# PiHatSandwich-v2.net
KiCad netlist of a schematic drawn in EAGLE
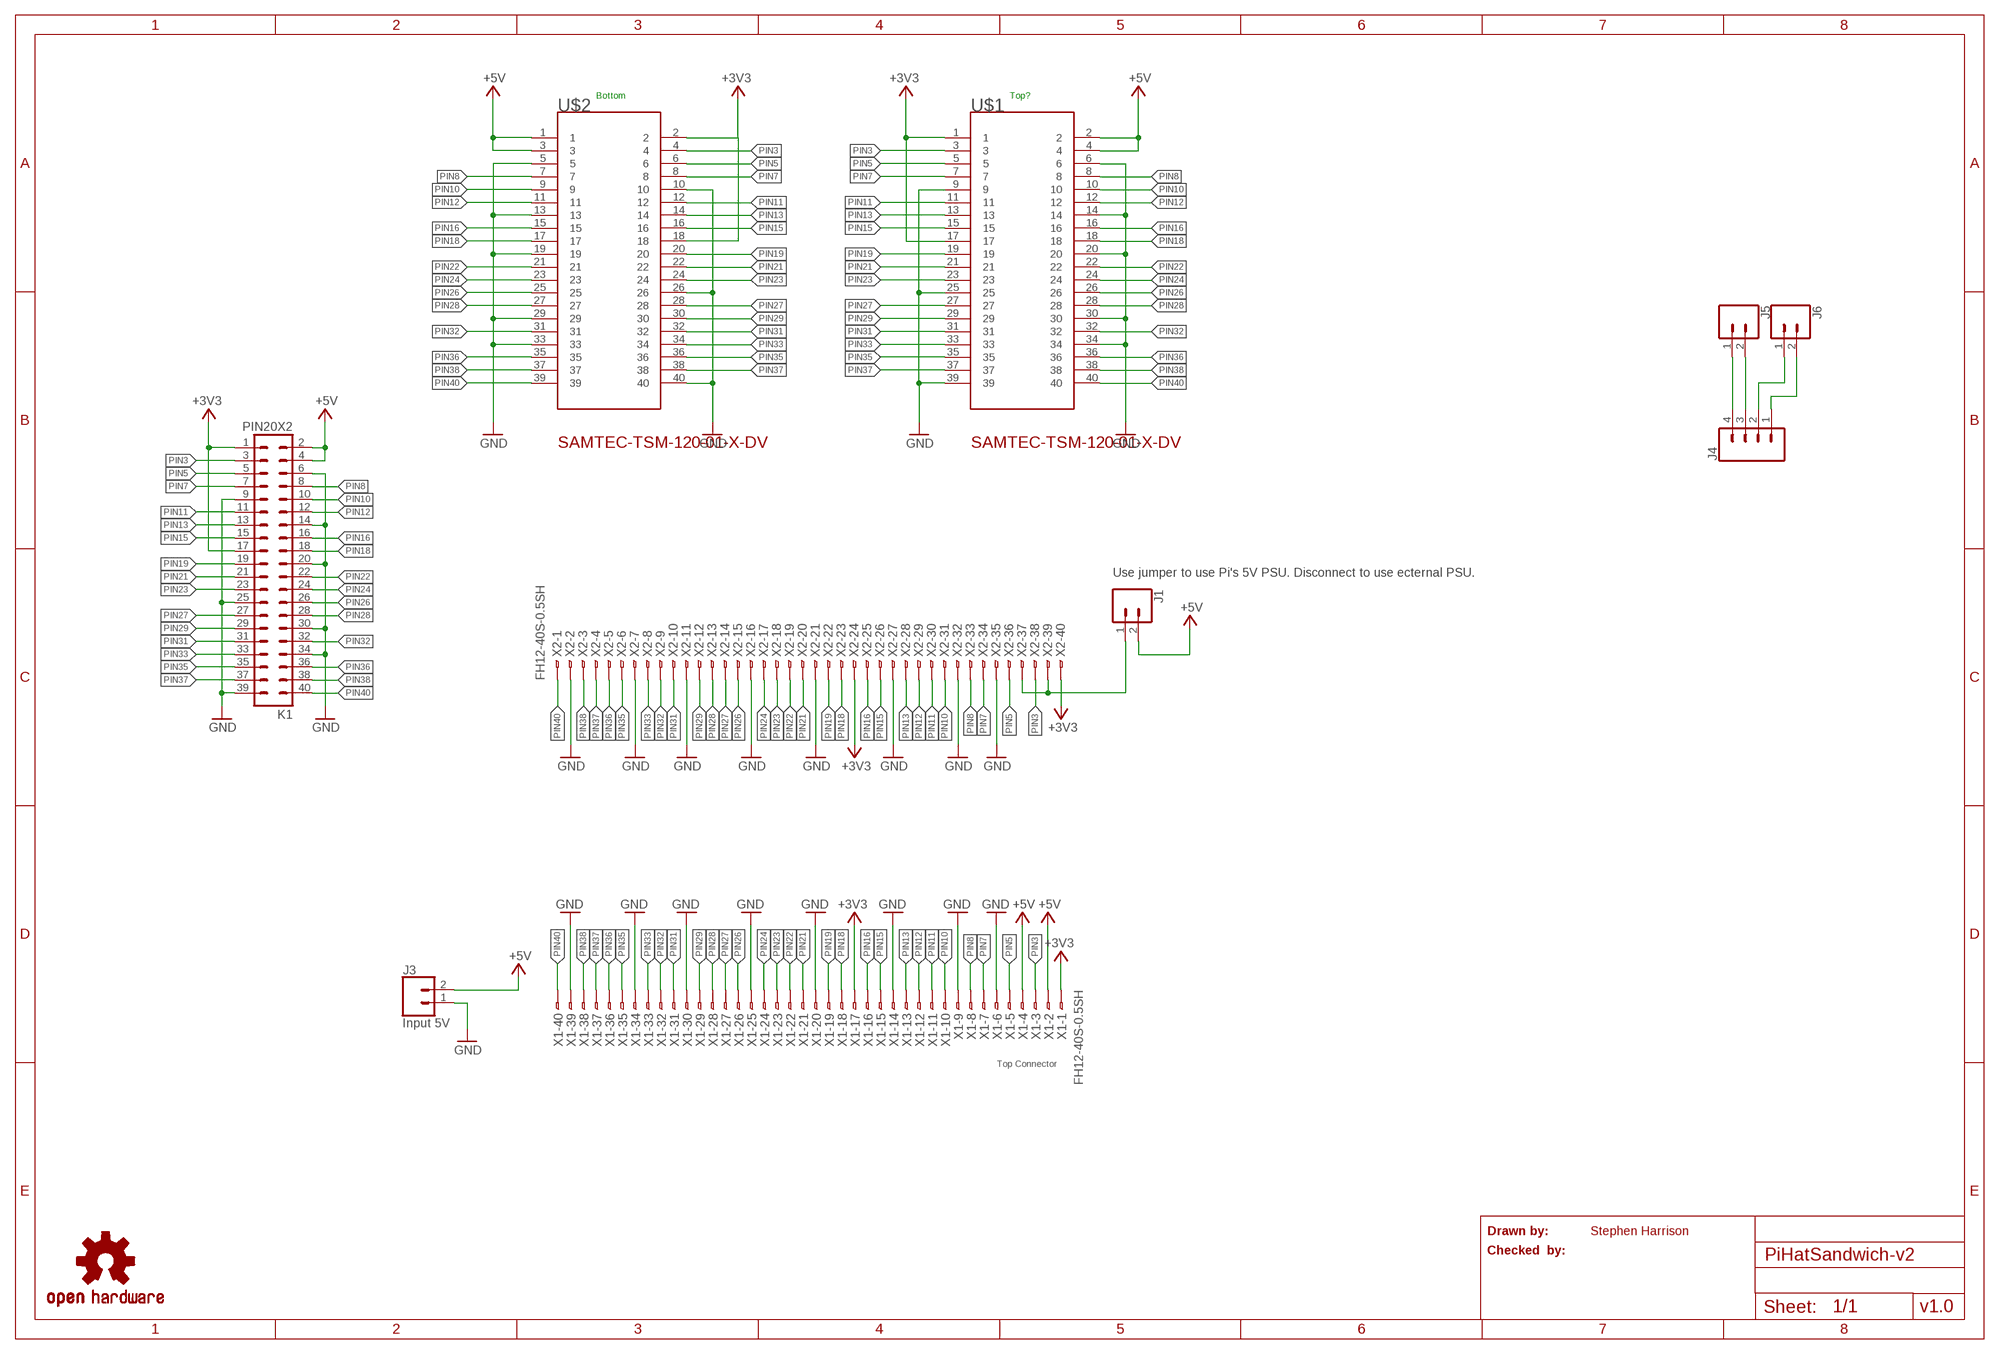
[diagram p0: schematic, sheet 1]

(export (version "E")
  (design (tool "Eeschema 10.0.6"))
  (components
    (comp (ref "J1")
      (value "CONN_02")
      (footprint "eagle-import:1X02")
      (libsource (lib "eagle-import") (part "CONN_02"))
    )
    (comp (ref "J3")
      (value "Input 5V")
      (footprint "eagle-import:MOLEX-1X2")
      (libsource (lib "eagle-import") (part "CONN_02POLAR"))
    )
    (comp (ref "J4")
      (value "CONN_04POLAR")
      (footprint "eagle-import:MOLEX-1X4")
      (libsource (lib "eagle-import") (part "CONN_04POLAR"))
    )
    (comp (ref "J5")
      (value "CONN_02")
      (footprint "eagle-import:1X02")
      (libsource (lib "eagle-import") (part "CONN_02"))
    )
    (comp (ref "J6")
      (value "CONN_02")
      (footprint "eagle-import:1X02")
      (libsource (lib "eagle-import") (part "CONN_02"))
    )
    (comp (ref "K1")
      (value "PIN20X2")
      (footprint "eagle-import:PIN_20X2")
      (libsource (lib "eagle-import") (part "PIN20X2"))
    )
    (comp (ref "LOGO1")
      (value "OSHW-LOGOL")
      (footprint "eagle-import:OSHW-LOGO-L")
      (libsource (lib "eagle-import") (part "OSHW-LOGOL"))
    )
    (comp (ref "U$1")
      (value "SAMTEC-TSM-120-01-X-DVJ")
      (footprint "eagle-import:SAMTEC-TSM-120-01-X-DV")
      (fields (field (name "MF") "Samtec") (field (name "MP") "TSM-120-01-S-DV-M"))
      (libsource (lib "eagle-import") (part "SAMTEC-TSM-120-01-X-DVJ"))
    )
    (comp (ref "U$2")
      (value "SAMTEC-TSM-120-01-X-DVJ")
      (footprint "eagle-import:SAMTEC-TSM-120-01-X-DV")
      (fields (field (name "MF") "Samtec") (field (name "MP") "TSM-120-01-S-DV-M"))
      (libsource (lib "eagle-import") (part "SAMTEC-TSM-120-01-X-DVJ"))
    )
    (comp (ref "X1")
      (value "FH12-40S-0.5SH")
      (footprint "eagle-import:FH12-40S-0.5SH")
      (fields (field (name "MPN") "FH12-40S-0.5SH(55)"))
      (libsource (lib "eagle-import") (part "FH12-40S-0.5SH"))
    )
    (comp (ref "X2")
      (value "FH12-40S-0.5SH")
      (footprint "eagle-import:FH12-40S-0.5SH")
      (fields (field (name "MPN") "FH12-40S-0.5SH(55)"))
      (libsource (lib "eagle-import") (part "FH12-40S-0.5SH"))
    )
  )
  (nets
    (net (code "1") (name "+3V3") (class "Default")
      (node (ref "K1") (pin "1") (pinfunction "1_1") (pintype "passive"))
      (node (ref "K1") (pin "17") (pinfunction "17_17") (pintype "passive"))
      (node (ref "U$1") (pin "1") (pinfunction "1_1") (pintype "passive"))
      (node (ref "U$1") (pin "17") (pinfunction "17_17") (pintype "passive"))
      (node (ref "U$2") (pin "18") (pinfunction "18_18") (pintype "passive"))
      (node (ref "U$2") (pin "2") (pinfunction "2_2") (pintype "passive"))
      (node (ref "X1") (pin "1") (pinfunction "1_1") (pintype "passive"))
      (node (ref "X1") (pin "17") (pinfunction "1_17") (pintype "passive"))
      (node (ref "X2") (pin "24") (pinfunction "1_24") (pintype "passive"))
      (node (ref "X2") (pin "40") (pinfunction "1_40") (pintype "passive"))
    )
    (net (code "2") (name "+5V") (class "Default")
      (node (ref "J1") (pin "2") (pinfunction "2_2") (pintype "passive"))
      (node (ref "J3") (pin "2") (pinfunction "2_2") (pintype "passive"))
      (node (ref "K1") (pin "2") (pinfunction "2_2") (pintype "passive"))
      (node (ref "K1") (pin "4") (pinfunction "4_4") (pintype "passive"))
      (node (ref "U$1") (pin "2") (pinfunction "2_2") (pintype "passive"))
      (node (ref "U$1") (pin "4") (pinfunction "4_4") (pintype "passive"))
      (node (ref "U$2") (pin "1") (pinfunction "1_1") (pintype "passive"))
      (node (ref "U$2") (pin "3") (pinfunction "3_3") (pintype "passive"))
      (node (ref "X1") (pin "2") (pinfunction "1_2") (pintype "passive"))
      (node (ref "X1") (pin "4") (pinfunction "1_4") (pintype "passive"))
    )
    (net (code "3") (name "GND") (class "Default")
      (node (ref "J3") (pin "1") (pinfunction "1_1") (pintype "passive"))
      (node (ref "K1") (pin "14") (pinfunction "14_14") (pintype "passive"))
      (node (ref "K1") (pin "20") (pinfunction "20_20") (pintype "passive"))
      (node (ref "K1") (pin "25") (pinfunction "25_25") (pintype "passive"))
      (node (ref "K1") (pin "30") (pinfunction "30_30") (pintype "passive"))
      (node (ref "K1") (pin "34") (pinfunction "34_34") (pintype "passive"))
      (node (ref "K1") (pin "39") (pinfunction "39_39") (pintype "passive"))
      (node (ref "K1") (pin "6") (pinfunction "6_6") (pintype "passive"))
      (node (ref "K1") (pin "9") (pinfunction "9_9") (pintype "passive"))
      (node (ref "U$1") (pin "14") (pinfunction "14_14") (pintype "passive"))
      (node (ref "U$1") (pin "20") (pinfunction "20_20") (pintype "passive"))
      (node (ref "U$1") (pin "25") (pinfunction "25_25") (pintype "passive"))
      (node (ref "U$1") (pin "30") (pinfunction "30_30") (pintype "passive"))
      (node (ref "U$1") (pin "34") (pinfunction "34_34") (pintype "passive"))
      (node (ref "U$1") (pin "39") (pinfunction "39_39") (pintype "passive"))
      (node (ref "U$1") (pin "6") (pinfunction "6_6") (pintype "passive"))
      (node (ref "U$1") (pin "9") (pinfunction "9_9") (pintype "passive"))
      (node (ref "U$2") (pin "10") (pinfunction "10_10") (pintype "passive"))
      (node (ref "U$2") (pin "13") (pinfunction "13_13") (pintype "passive"))
      (node (ref "U$2") (pin "19") (pinfunction "19_19") (pintype "passive"))
      (node (ref "U$2") (pin "26") (pinfunction "26_26") (pintype "passive"))
      (node (ref "U$2") (pin "29") (pinfunction "29_29") (pintype "passive"))
      (node (ref "U$2") (pin "33") (pinfunction "33_33") (pintype "passive"))
      (node (ref "U$2") (pin "40") (pinfunction "40_40") (pintype "passive"))
      (node (ref "U$2") (pin "5") (pinfunction "5_5") (pintype "passive"))
      (node (ref "X1") (pin "14") (pinfunction "1_14") (pintype "passive"))
      (node (ref "X1") (pin "20") (pinfunction "1_20") (pintype "passive"))
      (node (ref "X1") (pin "25") (pinfunction "1_25") (pintype "passive"))
      (node (ref "X1") (pin "30") (pinfunction "1_30") (pintype "passive"))
      (node (ref "X1") (pin "34") (pinfunction "1_34") (pintype "passive"))
      (node (ref "X1") (pin "39") (pinfunction "1_39") (pintype "passive"))
      (node (ref "X1") (pin "6") (pinfunction "1_6") (pintype "passive"))
      (node (ref "X1") (pin "9") (pinfunction "1_9") (pintype "passive"))
      (node (ref "X2") (pin "11") (pinfunction "1_11") (pintype "passive"))
      (node (ref "X2") (pin "16") (pinfunction "1_16") (pintype "passive"))
      (node (ref "X2") (pin "2") (pinfunction "1_2") (pintype "passive"))
      (node (ref "X2") (pin "21") (pinfunction "1_21") (pintype "passive"))
      (node (ref "X2") (pin "27") (pinfunction "1_27") (pintype "passive"))
      (node (ref "X2") (pin "32") (pinfunction "1_32") (pintype "passive"))
      (node (ref "X2") (pin "35") (pinfunction "1_35") (pintype "passive"))
      (node (ref "X2") (pin "7") (pinfunction "1_7") (pintype "passive"))
    )
    (net (code "4") (name "Net-(J4-Pad1)") (class "Default")
      (node (ref "J4") (pin "1") (pinfunction "1_1") (pintype "passive"))
      (node (ref "J6") (pin "2") (pinfunction "2_2") (pintype "passive"))
    )
    (net (code "5") (name "Net-(J4-Pad2)") (class "Default")
      (node (ref "J4") (pin "2") (pinfunction "2_2") (pintype "passive"))
      (node (ref "J6") (pin "1") (pinfunction "1_1") (pintype "passive"))
    )
    (net (code "6") (name "Net-(J4-Pad3)") (class "Default")
      (node (ref "J4") (pin "3") (pinfunction "3_3") (pintype "passive"))
      (node (ref "J5") (pin "2") (pinfunction "2_2") (pintype "passive"))
    )
    (net (code "7") (name "Net-(J4-Pad4)") (class "Default")
      (node (ref "J4") (pin "4") (pinfunction "4_4") (pintype "passive"))
      (node (ref "J5") (pin "1") (pinfunction "1_1") (pintype "passive"))
    )
    (net (code "8") (name "Net-(X2AE-1)") (class "Default")
      (node (ref "J1") (pin "1") (pinfunction "1_1") (pintype "passive"))
      (node (ref "X2") (pin "37") (pinfunction "1_37") (pintype "passive"))
      (node (ref "X2") (pin "39") (pinfunction "1_39") (pintype "passive"))
    )
    (net (code "9") (name "PIN3") (class "Default")
      (node (ref "K1") (pin "3") (pinfunction "3_3") (pintype "passive"))
      (node (ref "U$1") (pin "3") (pinfunction "3_3") (pintype "passive"))
      (node (ref "U$2") (pin "4") (pinfunction "4_4") (pintype "passive"))
      (node (ref "X1") (pin "3") (pinfunction "1_3") (pintype "passive"))
      (node (ref "X2") (pin "38") (pinfunction "1_38") (pintype "passive"))
    )
    (net (code "10") (name "PIN5") (class "Default")
      (node (ref "K1") (pin "5") (pinfunction "5_5") (pintype "passive"))
      (node (ref "U$1") (pin "5") (pinfunction "5_5") (pintype "passive"))
      (node (ref "U$2") (pin "6") (pinfunction "6_6") (pintype "passive"))
      (node (ref "X1") (pin "5") (pinfunction "1_5") (pintype "passive"))
      (node (ref "X2") (pin "36") (pinfunction "1_36") (pintype "passive"))
    )
    (net (code "11") (name "PIN7") (class "Default")
      (node (ref "K1") (pin "7") (pinfunction "7_7") (pintype "passive"))
      (node (ref "U$1") (pin "7") (pinfunction "7_7") (pintype "passive"))
      (node (ref "U$2") (pin "8") (pinfunction "8_8") (pintype "passive"))
      (node (ref "X1") (pin "7") (pinfunction "1_7") (pintype "passive"))
      (node (ref "X2") (pin "34") (pinfunction "1_34") (pintype "passive"))
    )
    (net (code "12") (name "PIN8") (class "Default")
      (node (ref "K1") (pin "8") (pinfunction "8_8") (pintype "passive"))
      (node (ref "U$1") (pin "8") (pinfunction "8_8") (pintype "passive"))
      (node (ref "U$2") (pin "7") (pinfunction "7_7") (pintype "passive"))
      (node (ref "X1") (pin "8") (pinfunction "1_8") (pintype "passive"))
      (node (ref "X2") (pin "33") (pinfunction "1_33") (pintype "passive"))
    )
    (net (code "13") (name "PIN10") (class "Default")
      (node (ref "K1") (pin "10") (pinfunction "10_10") (pintype "passive"))
      (node (ref "U$1") (pin "10") (pinfunction "10_10") (pintype "passive"))
      (node (ref "U$2") (pin "9") (pinfunction "9_9") (pintype "passive"))
      (node (ref "X1") (pin "10") (pinfunction "1_10") (pintype "passive"))
      (node (ref "X2") (pin "31") (pinfunction "1_31") (pintype "passive"))
    )
    (net (code "14") (name "PIN11") (class "Default")
      (node (ref "K1") (pin "11") (pinfunction "11_11") (pintype "passive"))
      (node (ref "U$1") (pin "11") (pinfunction "11_11") (pintype "passive"))
      (node (ref "U$2") (pin "12") (pinfunction "12_12") (pintype "passive"))
      (node (ref "X1") (pin "11") (pinfunction "1_11") (pintype "passive"))
      (node (ref "X2") (pin "30") (pinfunction "1_30") (pintype "passive"))
    )
    (net (code "15") (name "PIN12") (class "Default")
      (node (ref "K1") (pin "12") (pinfunction "12_12") (pintype "passive"))
      (node (ref "U$1") (pin "12") (pinfunction "12_12") (pintype "passive"))
      (node (ref "U$2") (pin "11") (pinfunction "11_11") (pintype "passive"))
      (node (ref "X1") (pin "12") (pinfunction "1_12") (pintype "passive"))
      (node (ref "X2") (pin "29") (pinfunction "1_29") (pintype "passive"))
    )
    (net (code "16") (name "PIN13") (class "Default")
      (node (ref "K1") (pin "13") (pinfunction "13_13") (pintype "passive"))
      (node (ref "U$1") (pin "13") (pinfunction "13_13") (pintype "passive"))
      (node (ref "U$2") (pin "14") (pinfunction "14_14") (pintype "passive"))
      (node (ref "X1") (pin "13") (pinfunction "1_13") (pintype "passive"))
      (node (ref "X2") (pin "28") (pinfunction "1_28") (pintype "passive"))
    )
    (net (code "17") (name "PIN15") (class "Default")
      (node (ref "K1") (pin "15") (pinfunction "15_15") (pintype "passive"))
      (node (ref "U$1") (pin "15") (pinfunction "15_15") (pintype "passive"))
      (node (ref "U$2") (pin "16") (pinfunction "16_16") (pintype "passive"))
      (node (ref "X1") (pin "15") (pinfunction "1_15") (pintype "passive"))
      (node (ref "X2") (pin "26") (pinfunction "1_26") (pintype "passive"))
    )
    (net (code "18") (name "PIN16") (class "Default")
      (node (ref "K1") (pin "16") (pinfunction "16_16") (pintype "passive"))
      (node (ref "U$1") (pin "16") (pinfunction "16_16") (pintype "passive"))
      (node (ref "U$2") (pin "15") (pinfunction "15_15") (pintype "passive"))
      (node (ref "X1") (pin "16") (pinfunction "1_16") (pintype "passive"))
      (node (ref "X2") (pin "25") (pinfunction "1_25") (pintype "passive"))
    )
    (net (code "19") (name "PIN18") (class "Default")
      (node (ref "K1") (pin "18") (pinfunction "18_18") (pintype "passive"))
      (node (ref "U$1") (pin "18") (pinfunction "18_18") (pintype "passive"))
      (node (ref "U$2") (pin "17") (pinfunction "17_17") (pintype "passive"))
      (node (ref "X1") (pin "18") (pinfunction "1_18") (pintype "passive"))
      (node (ref "X2") (pin "23") (pinfunction "1_23") (pintype "passive"))
    )
    (net (code "20") (name "PIN19") (class "Default")
      (node (ref "K1") (pin "19") (pinfunction "19_19") (pintype "passive"))
      (node (ref "U$1") (pin "19") (pinfunction "19_19") (pintype "passive"))
      (node (ref "U$2") (pin "20") (pinfunction "20_20") (pintype "passive"))
      (node (ref "X1") (pin "19") (pinfunction "1_19") (pintype "passive"))
      (node (ref "X2") (pin "22") (pinfunction "1_22") (pintype "passive"))
    )
    (net (code "21") (name "PIN21") (class "Default")
      (node (ref "K1") (pin "21") (pinfunction "21_21") (pintype "passive"))
      (node (ref "U$1") (pin "21") (pinfunction "21_21") (pintype "passive"))
      (node (ref "U$2") (pin "22") (pinfunction "22_22") (pintype "passive"))
      (node (ref "X1") (pin "21") (pinfunction "1_21") (pintype "passive"))
      (node (ref "X2") (pin "20") (pinfunction "1_20") (pintype "passive"))
    )
    (net (code "22") (name "PIN22") (class "Default")
      (node (ref "K1") (pin "22") (pinfunction "22_22") (pintype "passive"))
      (node (ref "U$1") (pin "22") (pinfunction "22_22") (pintype "passive"))
      (node (ref "U$2") (pin "21") (pinfunction "21_21") (pintype "passive"))
      (node (ref "X1") (pin "22") (pinfunction "1_22") (pintype "passive"))
      (node (ref "X2") (pin "19") (pinfunction "1_19") (pintype "passive"))
    )
    (net (code "23") (name "PIN23") (class "Default")
      (node (ref "K1") (pin "23") (pinfunction "23_23") (pintype "passive"))
      (node (ref "U$1") (pin "23") (pinfunction "23_23") (pintype "passive"))
      (node (ref "U$2") (pin "24") (pinfunction "24_24") (pintype "passive"))
      (node (ref "X1") (pin "23") (pinfunction "1_23") (pintype "passive"))
      (node (ref "X2") (pin "18") (pinfunction "1_18") (pintype "passive"))
    )
    (net (code "24") (name "PIN24") (class "Default")
      (node (ref "K1") (pin "24") (pinfunction "24_24") (pintype "passive"))
      (node (ref "U$1") (pin "24") (pinfunction "24_24") (pintype "passive"))
      (node (ref "U$2") (pin "23") (pinfunction "23_23") (pintype "passive"))
      (node (ref "X1") (pin "24") (pinfunction "1_24") (pintype "passive"))
      (node (ref "X2") (pin "17") (pinfunction "1_17") (pintype "passive"))
    )
    (net (code "25") (name "PIN26") (class "Default")
      (node (ref "K1") (pin "26") (pinfunction "26_26") (pintype "passive"))
      (node (ref "U$1") (pin "26") (pinfunction "26_26") (pintype "passive"))
      (node (ref "U$2") (pin "25") (pinfunction "25_25") (pintype "passive"))
      (node (ref "X1") (pin "26") (pinfunction "1_26") (pintype "passive"))
      (node (ref "X2") (pin "15") (pinfunction "1_15") (pintype "passive"))
    )
    (net (code "26") (name "PIN27") (class "Default")
      (node (ref "K1") (pin "27") (pinfunction "27_27") (pintype "passive"))
      (node (ref "U$1") (pin "27") (pinfunction "27_27") (pintype "passive"))
      (node (ref "U$2") (pin "28") (pinfunction "28_28") (pintype "passive"))
      (node (ref "X1") (pin "27") (pinfunction "1_27") (pintype "passive"))
      (node (ref "X2") (pin "14") (pinfunction "1_14") (pintype "passive"))
    )
    (net (code "27") (name "PIN28") (class "Default")
      (node (ref "K1") (pin "28") (pinfunction "28_28") (pintype "passive"))
      (node (ref "U$1") (pin "28") (pinfunction "28_28") (pintype "passive"))
      (node (ref "U$2") (pin "27") (pinfunction "27_27") (pintype "passive"))
      (node (ref "X1") (pin "28") (pinfunction "1_28") (pintype "passive"))
      (node (ref "X2") (pin "13") (pinfunction "1_13") (pintype "passive"))
    )
    (net (code "28") (name "PIN29") (class "Default")
      (node (ref "K1") (pin "29") (pinfunction "29_29") (pintype "passive"))
      (node (ref "U$1") (pin "29") (pinfunction "29_29") (pintype "passive"))
      (node (ref "U$2") (pin "30") (pinfunction "30_30") (pintype "passive"))
      (node (ref "X1") (pin "29") (pinfunction "1_29") (pintype "passive"))
      (node (ref "X2") (pin "12") (pinfunction "1_12") (pintype "passive"))
    )
    (net (code "29") (name "PIN31") (class "Default")
      (node (ref "K1") (pin "31") (pinfunction "31_31") (pintype "passive"))
      (node (ref "U$1") (pin "31") (pinfunction "31_31") (pintype "passive"))
      (node (ref "U$2") (pin "32") (pinfunction "32_32") (pintype "passive"))
      (node (ref "X1") (pin "31") (pinfunction "1_31") (pintype "passive"))
      (node (ref "X2") (pin "10") (pinfunction "1_10") (pintype "passive"))
    )
    (net (code "30") (name "PIN32") (class "Default")
      (node (ref "K1") (pin "32") (pinfunction "32_32") (pintype "passive"))
      (node (ref "U$1") (pin "32") (pinfunction "32_32") (pintype "passive"))
      (node (ref "U$2") (pin "31") (pinfunction "31_31") (pintype "passive"))
      (node (ref "X1") (pin "32") (pinfunction "1_32") (pintype "passive"))
      (node (ref "X2") (pin "9") (pinfunction "1_9") (pintype "passive"))
    )
    (net (code "31") (name "PIN33") (class "Default")
      (node (ref "K1") (pin "33") (pinfunction "33_33") (pintype "passive"))
      (node (ref "U$1") (pin "33") (pinfunction "33_33") (pintype "passive"))
      (node (ref "U$2") (pin "34") (pinfunction "34_34") (pintype "passive"))
      (node (ref "X1") (pin "33") (pinfunction "1_33") (pintype "passive"))
      (node (ref "X2") (pin "8") (pinfunction "1_8") (pintype "passive"))
    )
    (net (code "32") (name "PIN35") (class "Default")
      (node (ref "K1") (pin "35") (pinfunction "35_35") (pintype "passive"))
      (node (ref "U$1") (pin "35") (pinfunction "35_35") (pintype "passive"))
      (node (ref "U$2") (pin "36") (pinfunction "36_36") (pintype "passive"))
      (node (ref "X1") (pin "35") (pinfunction "1_35") (pintype "passive"))
      (node (ref "X2") (pin "6") (pinfunction "1_6") (pintype "passive"))
    )
    (net (code "33") (name "PIN36") (class "Default")
      (node (ref "K1") (pin "36") (pinfunction "36_36") (pintype "passive"))
      (node (ref "U$1") (pin "36") (pinfunction "36_36") (pintype "passive"))
      (node (ref "U$2") (pin "35") (pinfunction "35_35") (pintype "passive"))
      (node (ref "X1") (pin "36") (pinfunction "1_36") (pintype "passive"))
      (node (ref "X2") (pin "5") (pinfunction "1_5") (pintype "passive"))
    )
    (net (code "34") (name "PIN37") (class "Default")
      (node (ref "K1") (pin "37") (pinfunction "37_37") (pintype "passive"))
      (node (ref "U$1") (pin "37") (pinfunction "37_37") (pintype "passive"))
      (node (ref "U$2") (pin "38") (pinfunction "38_38") (pintype "passive"))
      (node (ref "X1") (pin "37") (pinfunction "1_37") (pintype "passive"))
      (node (ref "X2") (pin "4") (pinfunction "1_4") (pintype "passive"))
    )
    (net (code "35") (name "PIN38") (class "Default")
      (node (ref "K1") (pin "38") (pinfunction "38_38") (pintype "passive"))
      (node (ref "U$1") (pin "38") (pinfunction "38_38") (pintype "passive"))
      (node (ref "U$2") (pin "37") (pinfunction "37_37") (pintype "passive"))
      (node (ref "X1") (pin "38") (pinfunction "1_38") (pintype "passive"))
      (node (ref "X2") (pin "3") (pinfunction "1_3") (pintype "passive"))
    )
    (net (code "36") (name "PIN40") (class "Default")
      (node (ref "K1") (pin "40") (pinfunction "40_40") (pintype "passive"))
      (node (ref "U$1") (pin "40") (pinfunction "40_40") (pintype "passive"))
      (node (ref "U$2") (pin "39") (pinfunction "39_39") (pintype "passive"))
      (node (ref "X1") (pin "40") (pinfunction "1_40") (pintype "passive"))
      (node (ref "X2") (pin "1") (pinfunction "1_1") (pintype "passive"))
    )
  )
)
